# AuxHalfH.net
KiCad netlist of a schematic drawn in Altium Designer
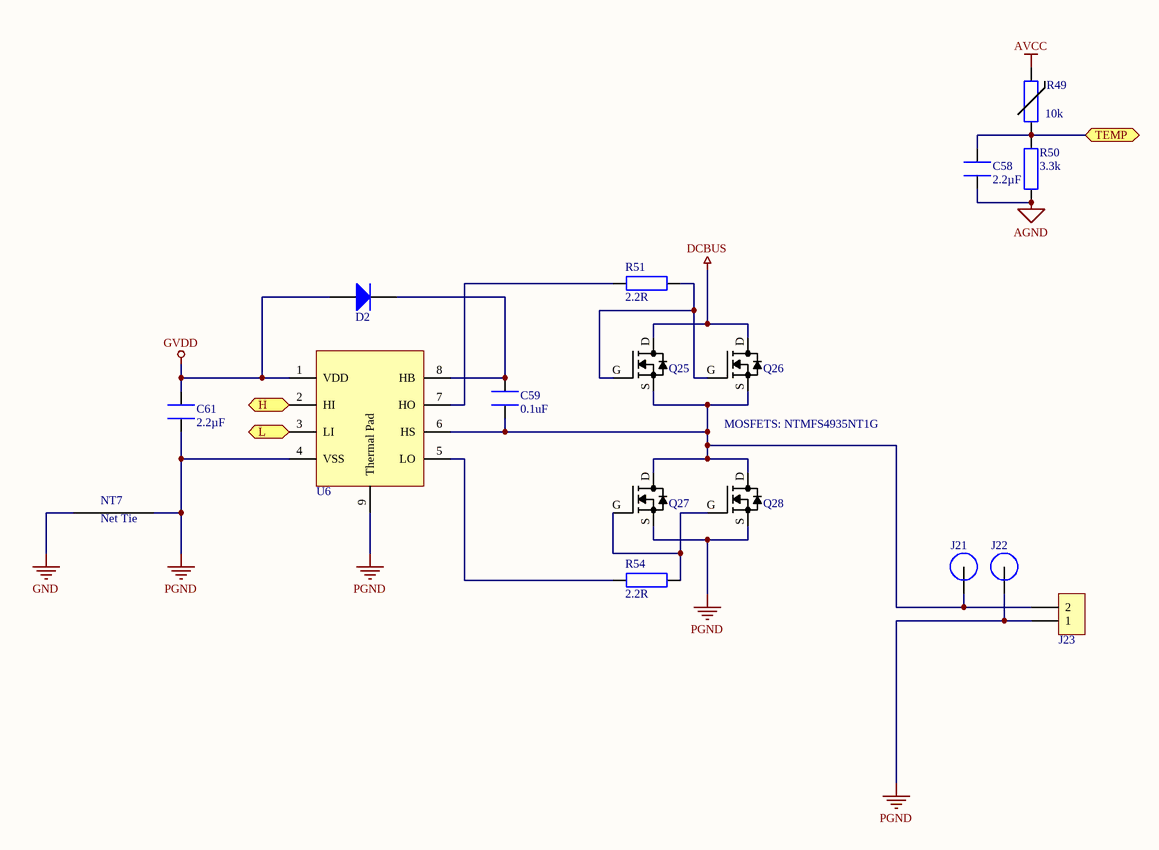
[diagram p0: AuxHalfH.SchDoc]

(export (version "E")
  (design (tool "Eeschema 10.0.6"))
  (components
    (comp (ref "C58")
      (value "2.2µF")
      (footprint "CAPC1608X09L")
      (description "CAP CER 2.2UF 16V X5R 0603")
      (fields
        (field (name "MANUFACTURER") "Murata Electronics North America")
        (field (name "MANUFACTURER PART NUMBER") "GRM188R61C225KE15D")
      )
      (libsource (lib "CustomComponents") (part "GRM188R61C225KE15D"))
    )
    (comp (ref "C59")
      (value "0.1uF")
      (footprint "CAPC1608X09L")
      (description "CAP CER 0.1UF 50V X7R 0603")
      (fields
        (field (name "MANUFACTURER") "Murata Electronics North America")
        (field (name "MANUFACTURER PART NUMBER") "GRM188R71H104KA93D")
      )
      (libsource (lib "CustomComponents") (part "GRM188R71H104KA93D"))
    )
    (comp (ref "C61")
      (value "2.2µF")
      (footprint "CAPC1608X09L")
      (description "CAP CER 2.2UF 16V X5R 0603")
      (fields
        (field (name "MANUFACTURER") "Murata Electronics North America")
        (field (name "MANUFACTURER PART NUMBER") "GRM188R61C225KE15D")
      )
      (libsource (lib "CustomComponents") (part "GRM188R61C225KE15D"))
    )
    (comp (ref "D2")
      (value "~")
      (footprint "DIOM2717X10N")
      (description "Rectifier Diode, Single, 40 V, 1 A, SOD-123FL, 2, 550 mV")
      (libsource (lib "CustomComponents") (part "MBR140SFT1G"))
    )
    (comp (ref "J21")
      (value "~")
      (footprint "M3 Spade Hole")
      (description "M3 Spade Terminal")
      (libsource (lib "CustomComponents") (part "M3 Spade Terminal"))
    )
    (comp (ref "J22")
      (value "~")
      (footprint "M3 Spade Hole")
      (description "M3 Spade Terminal")
      (libsource (lib "CustomComponents") (part "M3 Spade Terminal"))
    )
    (comp (ref "J23")
      (value "1868076")
      (footprint "1868076")
      (description "CONN TERM BLOCK 2POS 7.62MM")
      (fields (field (name "MANUFACTURER") "Phoenix Contact") (field (name "VOLTAGE") "300V"))
      (libsource (lib "CustomComponents") (part "1868076"))
    )
    (comp (ref "NT7")
      (value "0.25mm")
      (footprint "NetTie_0.25mm")
      (libsource (lib "CustomComponents") (part "NetTie_0.25mm"))
    )
    (comp (ref "Q25")
      (value "FILL_FOOTPRINT")
      (footprint "SO8FL_FILL")
      (description "MOSFET N-CH 30V 13A SO8FL")
      (fields
        (field (name "MANUFACTURER") "ON Semiconductor")
        (field (name "MANUFACTURER PART NUMBER") "NTMFS4935NT1G")
      )
      (libsource (lib "CustomComponents") (part "NTMFS4935NT1G"))
    )
    (comp (ref "Q26")
      (value "~")
      (footprint "SO8FL")
      (description "MOSFET N-CH 30V 13A SO8FL")
      (fields
        (field (name "MANUFACTURER") "ON Semiconductor")
        (field (name "MANUFACTURER PART NUMBER") "NTMFS4935NT1G")
      )
      (libsource (lib "CustomComponents") (part "NTMFS4935NT1G"))
    )
    (comp (ref "Q27")
      (value "~")
      (footprint "SO8FL")
      (description "MOSFET N-CH 30V 13A SO8FL")
      (fields
        (field (name "MANUFACTURER") "ON Semiconductor")
        (field (name "MANUFACTURER PART NUMBER") "NTMFS4935NT1G")
      )
      (libsource (lib "CustomComponents") (part "NTMFS4935NT1G"))
    )
    (comp (ref "Q28")
      (value "~")
      (footprint "SO8FL")
      (description "MOSFET N-CH 30V 13A SO8FL")
      (fields
        (field (name "MANUFACTURER") "ON Semiconductor")
        (field (name "MANUFACTURER PART NUMBER") "NTMFS4935NT1G")
      )
      (libsource (lib "CustomComponents") (part "NTMFS4935NT1G"))
    )
    (comp (ref "R49")
      (value "10k")
      (footprint "RESC1005X40N")
      (description "THERMISTOR 10K OHM NTC 0402 SMD")
      (libsource (lib "CustomComponents") (part "NCP15XH103F03RC"))
    )
    (comp (ref "R50")
      (value "3.3k")
      (footprint "RESC1608X55N")
      (description "RES SMD 3.3K OHM 1% 1/10W 0603")
      (fields
        (field (name "MANUFACTURER") "Yageo")
        (field (name "MANUFACTURER PART NUMBER") "RC0603FR-073K3L")
      )
      (libsource (lib "CustomComponents") (part "RC0603FR-073K3L"))
    )
    (comp (ref "R51")
      (value "2.2R")
      (footprint "RESC1608X55N")
      (description "RES SMD 2.2 OHM 1% 1/10W 0603")
      (fields
        (field (name "MANUFACTURER") "Yageo")
        (field (name "MANUFACTURER PART NUMBER") "RC0603FR-072R2L")
      )
      (libsource (lib "CustomComponents") (part "RC0603FR-072R2L"))
    )
    (comp (ref "R54")
      (value "2.2R")
      (footprint "RESC1608X55N")
      (description "RES SMD 2.2 OHM 1% 1/10W 0603")
      (fields
        (field (name "MANUFACTURER") "Yageo")
        (field (name "MANUFACTURER PART NUMBER") "RC0603FR-072R2L")
      )
      (libsource (lib "CustomComponents") (part "RC0603FR-072R2L"))
    )
    (comp (ref "U6")
      (value "~")
      (footprint "SON80P400X80_HS-9N")
      (description "DRIVER, MOSFET, HALF BRIDGE, WSON-8, 1A")
      (libsource (lib "CustomComponents") (part "LM5109BSD/NOPB"))
    )
  )
  (nets
    (net (code "1") (name "/H") (class "Default")
      (node (ref "U6") (pin "2") (pinfunction "HI_2") (pintype "passive"))
    )
    (net (code "2") (name "/L") (class "Default")
      (node (ref "U6") (pin "3") (pinfunction "LI_3") (pintype "passive"))
    )
    (net (code "3") (name "/TEMP") (class "Default")
      (node (ref "C58") (pin "2") (pinfunction "2_2") (pintype "passive"))
      (node (ref "R49") (pin "1") (pinfunction "0_1") (pintype "passive"))
      (node (ref "R50") (pin "1") (pinfunction "0_1") (pintype "passive"))
    )
    (net (code "4") (name "AGND") (class "Default")
      (node (ref "C58") (pin "1") (pinfunction "1_1") (pintype "passive"))
      (node (ref "R50") (pin "2") (pinfunction "0_2") (pintype "passive"))
    )
    (net (code "5") (name "AVCC") (class "Default")
      (node (ref "R49") (pin "2") (pinfunction "0_2") (pintype "passive"))
    )
    (net (code "6") (name "DCBUS") (class "Default")
      (node (ref "Q25") (pin "D") (pinfunction "D_D") (pintype "passive"))
      (node (ref "Q26") (pin "D") (pinfunction "D_D") (pintype "passive"))
    )
    (net (code "7") (name "GND") (class "Default") (node (ref "NT7") (pin "1") (pintype "passive")))
    (net (code "8") (name "GVDD") (class "Default")
      (node (ref "C61") (pin "2") (pinfunction "2_2") (pintype "passive"))
      (node (ref "D2") (pin "A") (pinfunction "A_A") (pintype "passive"))
      (node (ref "U6") (pin "1") (pinfunction "VDD_1") (pintype "passive"))
    )
    (net (code "9") (name "Net-(Q25-PadG)") (class "Default")
      (node (ref "Q25") (pin "G") (pinfunction "G_G") (pintype "passive"))
      (node (ref "Q26") (pin "G") (pinfunction "G_G") (pintype "passive"))
      (node (ref "R51") (pin "2") (pinfunction "0_2") (pintype "passive"))
    )
    (net (code "10") (name "Net-(Q27-PadG)") (class "Default")
      (node (ref "Q27") (pin "G") (pinfunction "G_G") (pintype "passive"))
      (node (ref "Q28") (pin "G") (pinfunction "G_G") (pintype "passive"))
      (node (ref "R54") (pin "2") (pinfunction "0_2") (pintype "passive"))
    )
    (net (code "11") (name "Net-(U6-HB)") (class "Default")
      (node (ref "C59") (pin "1") (pinfunction "1_1") (pintype "passive"))
      (node (ref "D2") (pin "K") (pinfunction "K_K") (pintype "passive"))
      (node (ref "U6") (pin "8") (pinfunction "HB_8") (pintype "passive"))
    )
    (net (code "12") (name "Net-(U6-HO)") (class "Default")
      (node (ref "R51") (pin "1") (pinfunction "0_1") (pintype "passive"))
      (node (ref "U6") (pin "7") (pinfunction "HO_7") (pintype "passive"))
    )
    (net (code "13") (name "Net-(U6-HS)") (class "Default")
      (node (ref "C59") (pin "2") (pinfunction "2_2") (pintype "passive"))
      (node (ref "J21") (pin "1") (pinfunction "1_1") (pintype "passive"))
      (node (ref "J23") (pin "2") (pinfunction "2_2") (pintype "passive"))
      (node (ref "Q25") (pin "S") (pinfunction "S_S") (pintype "passive"))
      (node (ref "Q26") (pin "S") (pinfunction "S_S") (pintype "passive"))
      (node (ref "Q27") (pin "D") (pinfunction "D_D") (pintype "passive"))
      (node (ref "Q28") (pin "D") (pinfunction "D_D") (pintype "passive"))
      (node (ref "U6") (pin "6") (pinfunction "HS_6") (pintype "passive"))
    )
    (net (code "14") (name "Net-(U6-LO)") (class "Default")
      (node (ref "R54") (pin "1") (pinfunction "0_1") (pintype "passive"))
      (node (ref "U6") (pin "5") (pinfunction "LO_5") (pintype "passive"))
    )
    (net (code "15") (name "PGND") (class "Default")
      (node (ref "C61") (pin "1") (pinfunction "1_1") (pintype "passive"))
      (node (ref "J22") (pin "1") (pinfunction "1_1") (pintype "passive"))
      (node (ref "J23") (pin "1") (pinfunction "1_1") (pintype "passive"))
      (node (ref "NT7") (pin "2") (pintype "passive"))
      (node (ref "Q27") (pin "S") (pinfunction "S_S") (pintype "passive"))
      (node (ref "Q28") (pin "S") (pinfunction "S_S") (pintype "passive"))
      (node (ref "U6") (pin "4") (pinfunction "VSS_4") (pintype "passive"))
      (node (ref "U6") (pin "9") (pinfunction "Thermal_Pad_9") (pintype "passive"))
    )
  )
)
